# SCH_Kit_Sumo_Bot_2023-11-08.net
KiCad netlist of a schematic drawn in EasyEDA
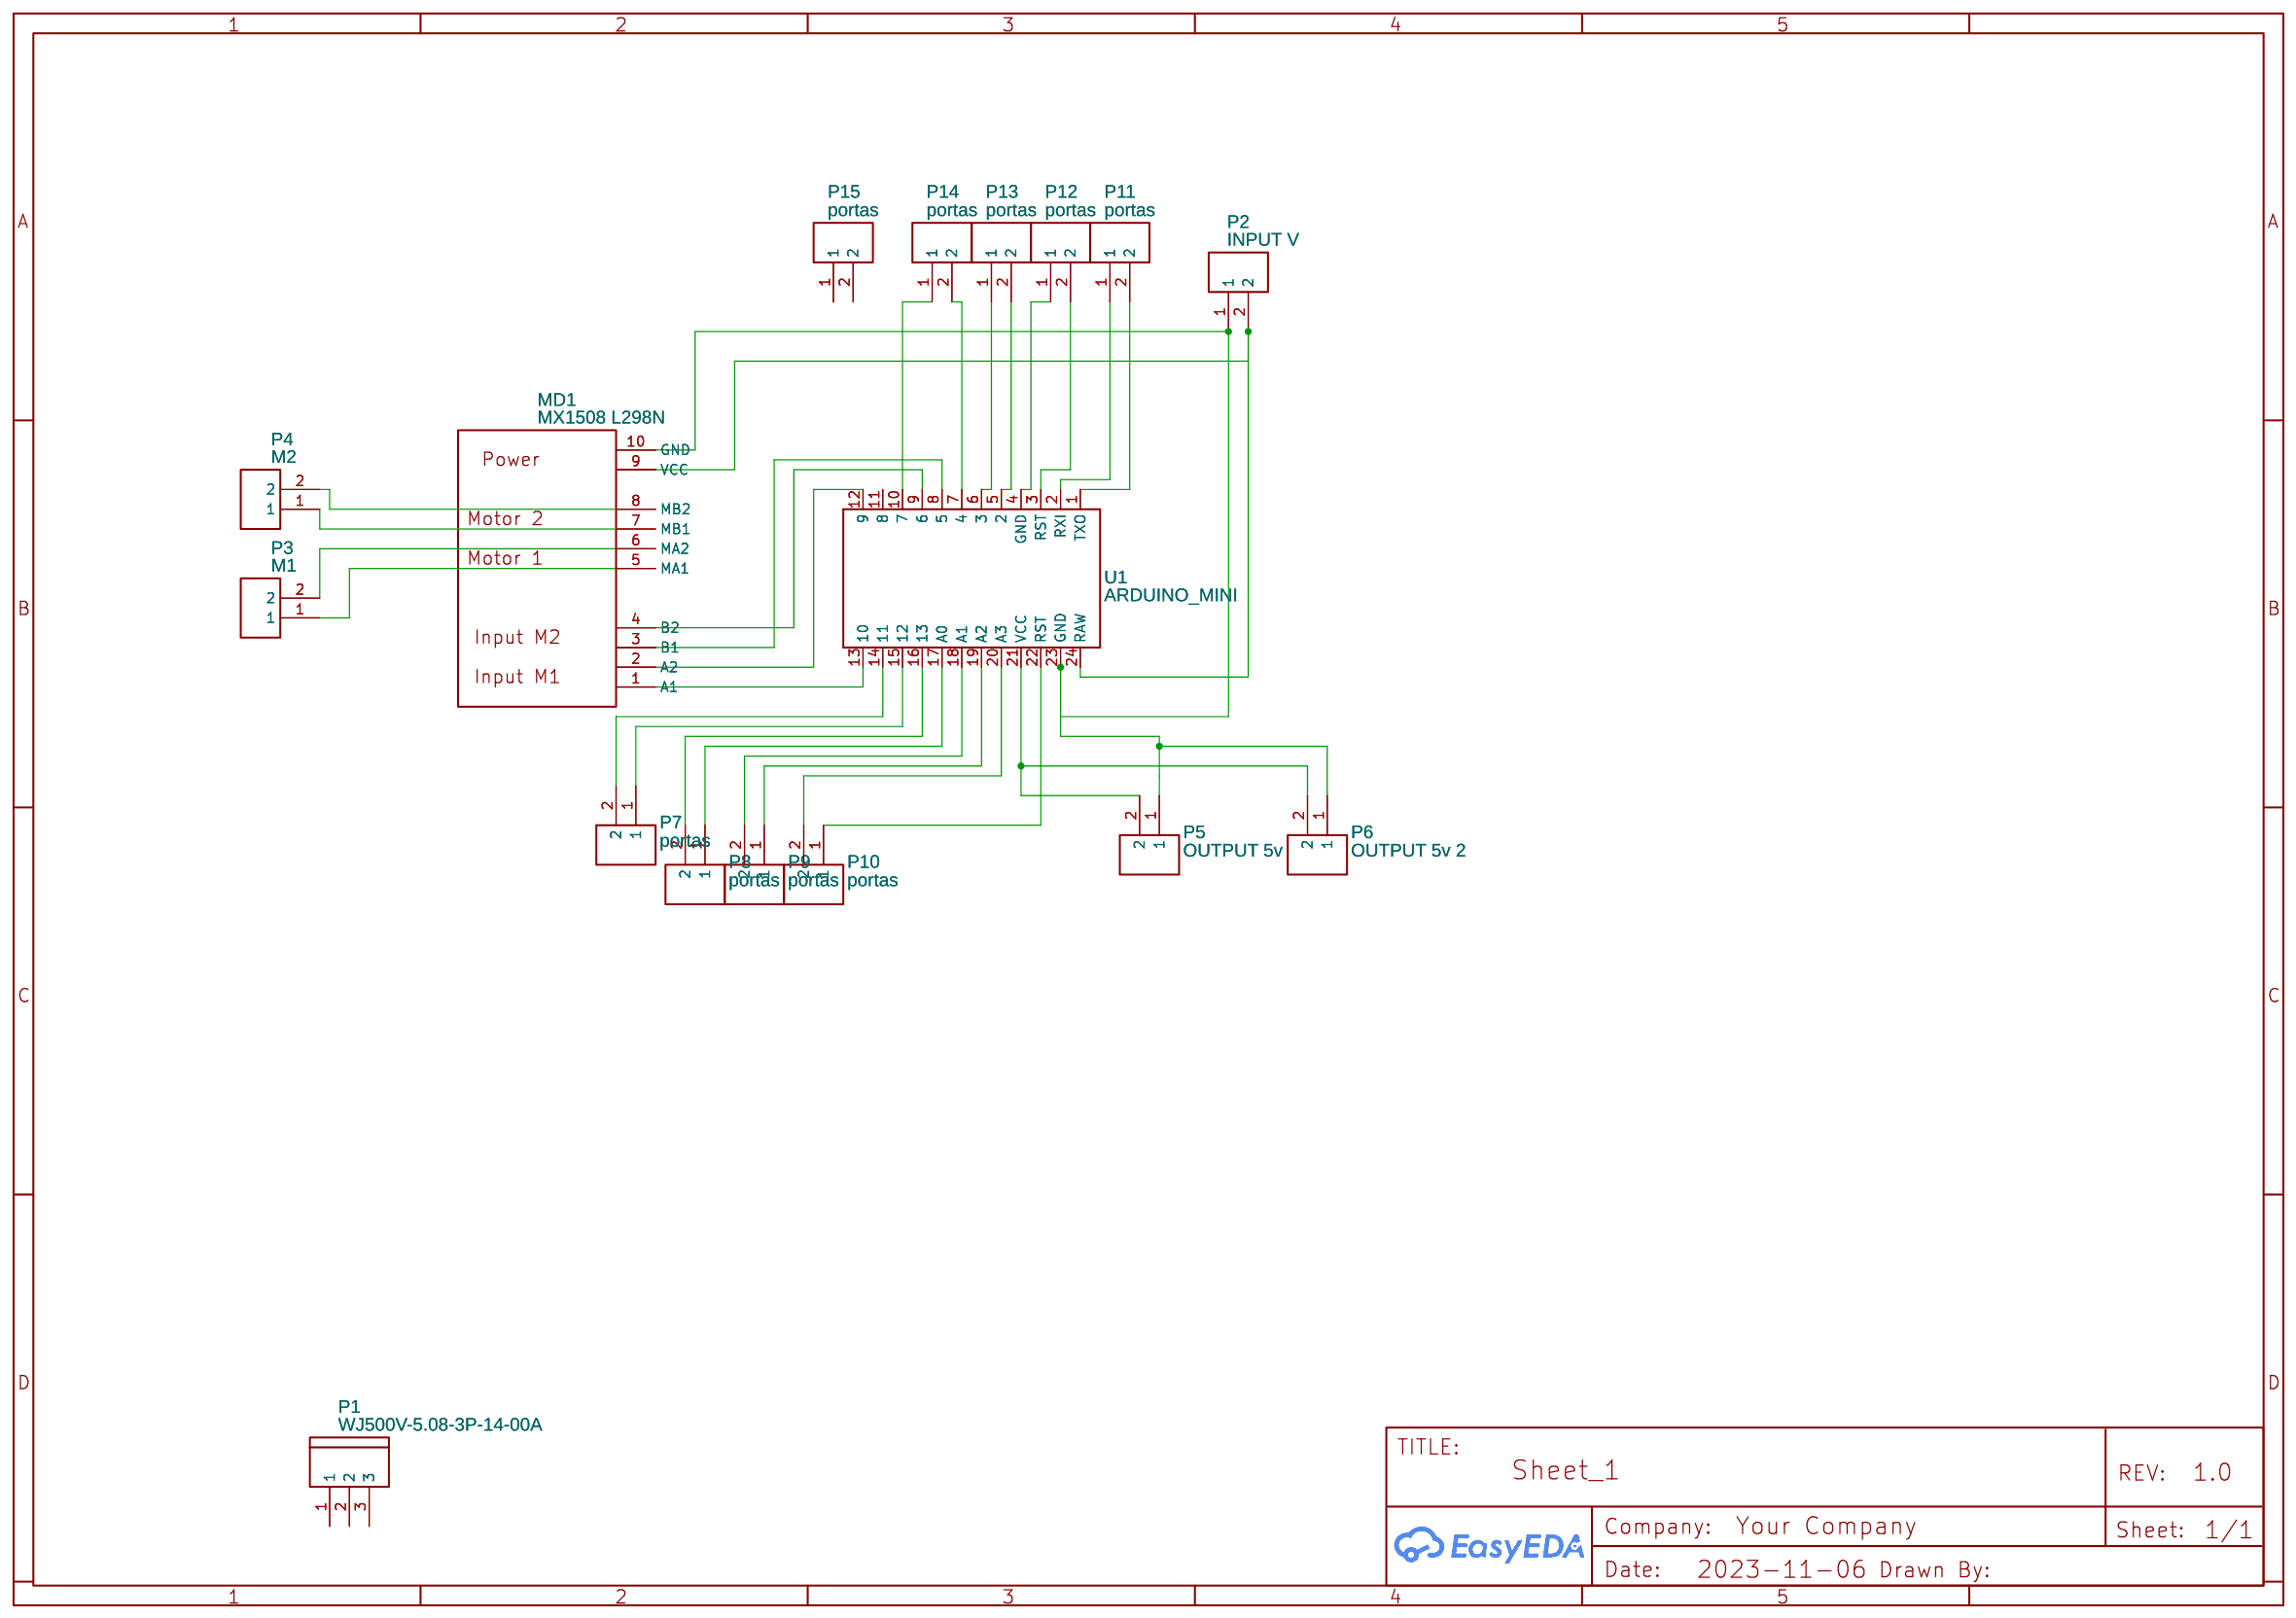
[diagram p0: schematic sheet]

(export (version "E")
  (design (tool "Eeschema 10.0.6"))
  (components
    (comp (ref "MD1") (value "MX1508 L298N") (libsource (lib "") (part "ZS-PWM MX1508 L298N PWM Module")))
    (comp (ref "P1")
      (value "WJ500V-5.08-3P-14-00A")
      (fields
        (field (name "Manufacturer Part") "WJ500V-5.08-3P")
        (field (name "Manufacturer") "KANGNEX(康奈克斯电气)")
      )
      (libsource (lib "") (part "WJ500V-5.08-3P-14-00A"))
    )
    (comp (ref "P2")
      (value "INPUT V")
      (fields
        (field (name "Manufacturer Part") "WJ500V-5.08-2P")
        (field (name "Manufacturer") "KANGNEX(康奈克斯电气)")
      )
      (libsource (lib "") (part "WJ500V-5.08-2P-14-00A_1"))
    )
    (comp (ref "P3")
      (value "M1")
      (fields
        (field (name "Manufacturer Part") "WJ500V-5.08-2P")
        (field (name "Manufacturer") "KANGNEX(康奈克斯电气)")
      )
      (libsource (lib "") (part "WJ500V-5.08-2P-14-00A_2"))
    )
    (comp (ref "P4")
      (value "M2")
      (fields
        (field (name "Manufacturer Part") "WJ500V-5.08-2P")
        (field (name "Manufacturer") "KANGNEX(康奈克斯电气)")
      )
      (libsource (lib "") (part "WJ500V-5.08-2P-14-00A_2"))
    )
    (comp (ref "P5")
      (value "OUTPUT 5v")
      (fields
        (field (name "Manufacturer Part") "WJ500V-5.08-2P")
        (field (name "Manufacturer") "KANGNEX(康奈克斯电气)")
      )
      (libsource (lib "") (part "WJ500V-5.08-2P-14-00A"))
    )
    (comp (ref "P6")
      (value "OUTPUT 5v 2")
      (fields
        (field (name "Manufacturer Part") "WJ500V-5.08-2P")
        (field (name "Manufacturer") "KANGNEX(康奈克斯电气)")
      )
      (libsource (lib "") (part "WJ500V-5.08-2P-14-00A"))
    )
    (comp (ref "P7")
      (value "portas")
      (fields
        (field (name "Manufacturer Part") "WJ500V-5.08-2P")
        (field (name "Manufacturer") "KANGNEX(康奈克斯电气)")
      )
      (libsource (lib "") (part "WJ500V-5.08-2P-14-00A"))
    )
    (comp (ref "P8")
      (value "portas")
      (fields
        (field (name "Manufacturer Part") "WJ500V-5.08-2P")
        (field (name "Manufacturer") "KANGNEX(康奈克斯电气)")
      )
      (libsource (lib "") (part "WJ500V-5.08-2P-14-00A"))
    )
    (comp (ref "P9")
      (value "portas")
      (fields
        (field (name "Manufacturer Part") "WJ500V-5.08-2P")
        (field (name "Manufacturer") "KANGNEX(康奈克斯电气)")
      )
      (libsource (lib "") (part "WJ500V-5.08-2P-14-00A"))
    )
    (comp (ref "P10")
      (value "portas")
      (fields
        (field (name "Manufacturer Part") "WJ500V-5.08-2P")
        (field (name "Manufacturer") "KANGNEX(康奈克斯电气)")
      )
      (libsource (lib "") (part "WJ500V-5.08-2P-14-00A"))
    )
    (comp (ref "P11")
      (value "portas")
      (fields
        (field (name "Manufacturer Part") "WJ500V-5.08-2P")
        (field (name "Manufacturer") "KANGNEX(康奈克斯电气)")
      )
      (libsource (lib "") (part "WJ500V-5.08-2P-14-00A_1"))
    )
    (comp (ref "P12")
      (value "portas")
      (fields
        (field (name "Manufacturer Part") "WJ500V-5.08-2P")
        (field (name "Manufacturer") "KANGNEX(康奈克斯电气)")
      )
      (libsource (lib "") (part "WJ500V-5.08-2P-14-00A_1"))
    )
    (comp (ref "P13")
      (value "portas")
      (fields
        (field (name "Manufacturer Part") "WJ500V-5.08-2P")
        (field (name "Manufacturer") "KANGNEX(康奈克斯电气)")
      )
      (libsource (lib "") (part "WJ500V-5.08-2P-14-00A_1"))
    )
    (comp (ref "P14")
      (value "portas")
      (fields
        (field (name "Manufacturer Part") "WJ500V-5.08-2P")
        (field (name "Manufacturer") "KANGNEX(康奈克斯电气)")
      )
      (libsource (lib "") (part "WJ500V-5.08-2P-14-00A_1"))
    )
    (comp (ref "P15")
      (value "portas")
      (fields
        (field (name "Manufacturer Part") "WJ500V-5.08-2P")
        (field (name "Manufacturer") "KANGNEX(康奈克斯电气)")
      )
      (libsource (lib "") (part "WJ500V-5.08-2P-14-00A_1"))
    )
    (comp (ref "U1") (value "ARDUINO_MINI") (libsource (lib "") (part "ARDUINO_MINI")))
  )
  (nets
    (net (code "1") (name "Net-(MD1-A1)") (class "Default")
      (node (ref "MD1") (pin "1") (pinfunction "A1_1") (pintype "input"))
      (node (ref "U1") (pin "13") (pinfunction "10_13") (pintype "unspecified"))
    )
    (net (code "2") (name "Net-(MD1-A2)") (class "Default")
      (node (ref "MD1") (pin "2") (pinfunction "A2_2") (pintype "input"))
      (node (ref "U1") (pin "12") (pinfunction "9_12") (pintype "unspecified"))
    )
    (net (code "3") (name "Net-(MD1-B1)") (class "Default")
      (node (ref "MD1") (pin "3") (pinfunction "B1_3") (pintype "input"))
      (node (ref "U1") (pin "8") (pinfunction "5_8") (pintype "unspecified"))
    )
    (net (code "4") (name "Net-(MD1-B2)") (class "Default")
      (node (ref "MD1") (pin "4") (pinfunction "B2_4") (pintype "input"))
      (node (ref "U1") (pin "9") (pinfunction "6_9") (pintype "unspecified"))
    )
    (net (code "5") (name "Net-(MD1-GND)") (class "Default")
      (node (ref "MD1") (pin "10") (pinfunction "GND_10") (pintype "passive"))
      (node (ref "P2") (pin "1") (pinfunction "1_1") (pintype "unspecified"))
      (node (ref "P5") (pin "1") (pinfunction "1_1") (pintype "unspecified"))
      (node (ref "P6") (pin "1") (pinfunction "1_1") (pintype "unspecified"))
      (node (ref "U1") (pin "23") (pinfunction "GND_23") (pintype "unspecified"))
    )
    (net (code "6") (name "Net-(MD1-MA1)") (class "Default")
      (node (ref "MD1") (pin "5") (pinfunction "MA1_5") (pintype "output"))
      (node (ref "P3") (pin "1") (pinfunction "1_1") (pintype "unspecified"))
    )
    (net (code "7") (name "Net-(MD1-MA2)") (class "Default")
      (node (ref "MD1") (pin "6") (pinfunction "MA2_6") (pintype "output"))
      (node (ref "P3") (pin "2") (pinfunction "2_2") (pintype "unspecified"))
    )
    (net (code "8") (name "Net-(MD1-MB1)") (class "Default")
      (node (ref "MD1") (pin "7") (pinfunction "MB1_7") (pintype "output"))
      (node (ref "P4") (pin "1") (pinfunction "1_1") (pintype "unspecified"))
    )
    (net (code "9") (name "Net-(MD1-MB2)") (class "Default")
      (node (ref "MD1") (pin "8") (pinfunction "MB2_8") (pintype "output"))
      (node (ref "P4") (pin "2") (pinfunction "2_2") (pintype "unspecified"))
    )
    (net (code "10") (name "Net-(MD1-VCC)") (class "Default")
      (node (ref "MD1") (pin "9") (pinfunction "VCC_9") (pintype "passive"))
      (node (ref "P2") (pin "2") (pinfunction "2_2") (pintype "unspecified"))
      (node (ref "U1") (pin "24") (pinfunction "RAW_24") (pintype "unspecified"))
    )
    (net (code "11") (name "Net-(P10-Pad1)") (class "Default")
      (node (ref "P10") (pin "1") (pinfunction "1_1") (pintype "unspecified"))
      (node (ref "U1") (pin "22") (pinfunction "RST_22") (pintype "unspecified"))
    )
    (net (code "12") (name "Net-(P12-Pad1)") (class "Default")
      (node (ref "P12") (pin "1") (pinfunction "1_1") (pintype "unspecified"))
      (node (ref "U1") (pin "4") (pinfunction "GND_4") (pintype "unspecified"))
    )
    (net (code "13") (name "Net-(P12-Pad2)") (class "Default")
      (node (ref "P12") (pin "2") (pinfunction "2_2") (pintype "unspecified"))
      (node (ref "U1") (pin "3") (pinfunction "RST_3") (pintype "unspecified"))
    )
    (net (code "14") (name "Net-(U1-2)") (class "Default")
      (node (ref "P13") (pin "2") (pinfunction "2_2") (pintype "unspecified"))
      (node (ref "U1") (pin "5") (pinfunction "2_5") (pintype "unspecified"))
    )
    (net (code "15") (name "Net-(U1-3)") (class "Default")
      (node (ref "P13") (pin "1") (pinfunction "1_1") (pintype "unspecified"))
      (node (ref "U1") (pin "6") (pinfunction "3_6") (pintype "unspecified"))
    )
    (net (code "16") (name "Net-(U1-4)") (class "Default")
      (node (ref "P14") (pin "2") (pinfunction "2_2") (pintype "unspecified"))
      (node (ref "U1") (pin "7") (pinfunction "4_7") (pintype "unspecified"))
    )
    (net (code "17") (name "Net-(U1-7)") (class "Default")
      (node (ref "P14") (pin "1") (pinfunction "1_1") (pintype "unspecified"))
      (node (ref "U1") (pin "10") (pinfunction "7_10") (pintype "unspecified"))
    )
    (net (code "18") (name "Net-(U1-11)") (class "Default")
      (node (ref "P7") (pin "2") (pinfunction "2_2") (pintype "unspecified"))
      (node (ref "U1") (pin "14") (pinfunction "11_14") (pintype "unspecified"))
    )
    (net (code "19") (name "Net-(U1-12)") (class "Default")
      (node (ref "P7") (pin "1") (pinfunction "1_1") (pintype "unspecified"))
      (node (ref "U1") (pin "15") (pinfunction "12_15") (pintype "unspecified"))
    )
    (net (code "20") (name "Net-(U1-13)") (class "Default")
      (node (ref "P8") (pin "2") (pinfunction "2_2") (pintype "unspecified"))
      (node (ref "U1") (pin "16") (pinfunction "13_16") (pintype "unspecified"))
    )
    (net (code "21") (name "Net-(U1-A0)") (class "Default")
      (node (ref "P8") (pin "1") (pinfunction "1_1") (pintype "unspecified"))
      (node (ref "U1") (pin "17") (pinfunction "A0_17") (pintype "unspecified"))
    )
    (net (code "22") (name "Net-(U1-A1)") (class "Default")
      (node (ref "P9") (pin "2") (pinfunction "2_2") (pintype "unspecified"))
      (node (ref "U1") (pin "18") (pinfunction "A1_18") (pintype "unspecified"))
    )
    (net (code "23") (name "Net-(U1-A2)") (class "Default")
      (node (ref "P9") (pin "1") (pinfunction "1_1") (pintype "unspecified"))
      (node (ref "U1") (pin "19") (pinfunction "A2_19") (pintype "unspecified"))
    )
    (net (code "24") (name "Net-(U1-A3)") (class "Default")
      (node (ref "P10") (pin "2") (pinfunction "2_2") (pintype "unspecified"))
      (node (ref "U1") (pin "20") (pinfunction "A3_20") (pintype "unspecified"))
    )
    (net (code "25") (name "Net-(U1-RXI)") (class "Default")
      (node (ref "P11") (pin "1") (pinfunction "1_1") (pintype "unspecified"))
      (node (ref "U1") (pin "2") (pinfunction "RXI_2") (pintype "unspecified"))
    )
    (net (code "26") (name "Net-(U1-TXO)") (class "Default")
      (node (ref "P11") (pin "2") (pinfunction "2_2") (pintype "unspecified"))
      (node (ref "U1") (pin "1") (pinfunction "TXO_1") (pintype "unspecified"))
    )
    (net (code "27") (name "Net-(U1-VCC)") (class "Default")
      (node (ref "P5") (pin "2") (pinfunction "2_2") (pintype "unspecified"))
      (node (ref "P6") (pin "2") (pinfunction "2_2") (pintype "unspecified"))
      (node (ref "U1") (pin "21") (pinfunction "VCC_21") (pintype "unspecified"))
    )
    (net (code "28") (name "unconnected-(P1-Pad1)") (class "Default")
      (node (ref "P1") (pin "1") (pinfunction "1_1") (pintype "unspecified"))
    )
    (net (code "29") (name "unconnected-(P1-Pad2)") (class "Default")
      (node (ref "P1") (pin "2") (pinfunction "2_2") (pintype "unspecified"))
    )
    (net (code "30") (name "unconnected-(P1-Pad3)") (class "Default")
      (node (ref "P1") (pin "3") (pinfunction "3_3") (pintype "unspecified"))
    )
    (net (code "31") (name "unconnected-(P15-Pad1)") (class "Default")
      (node (ref "P15") (pin "1") (pinfunction "1_1") (pintype "unspecified"))
    )
    (net (code "32") (name "unconnected-(P15-Pad2)") (class "Default")
      (node (ref "P15") (pin "2") (pinfunction "2_2") (pintype "unspecified"))
    )
    (net (code "33") (name "unconnected-(U1-8-Pad11)") (class "Default")
      (node (ref "U1") (pin "11") (pinfunction "8_11") (pintype "unspecified"))
    )
  )
)
